# tusb8041_hub_test.net
KiCad netlist of a schematic drawn in EAGLE
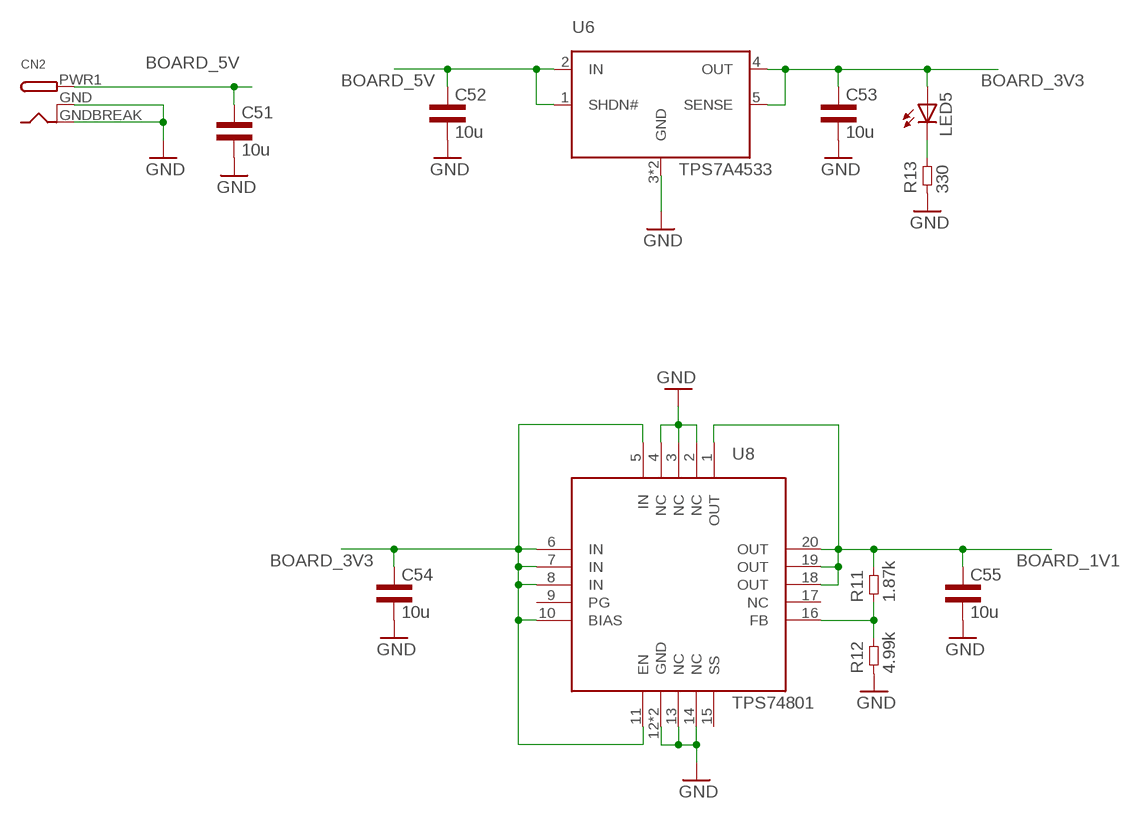
[diagram p0: schematic, sheet 1]
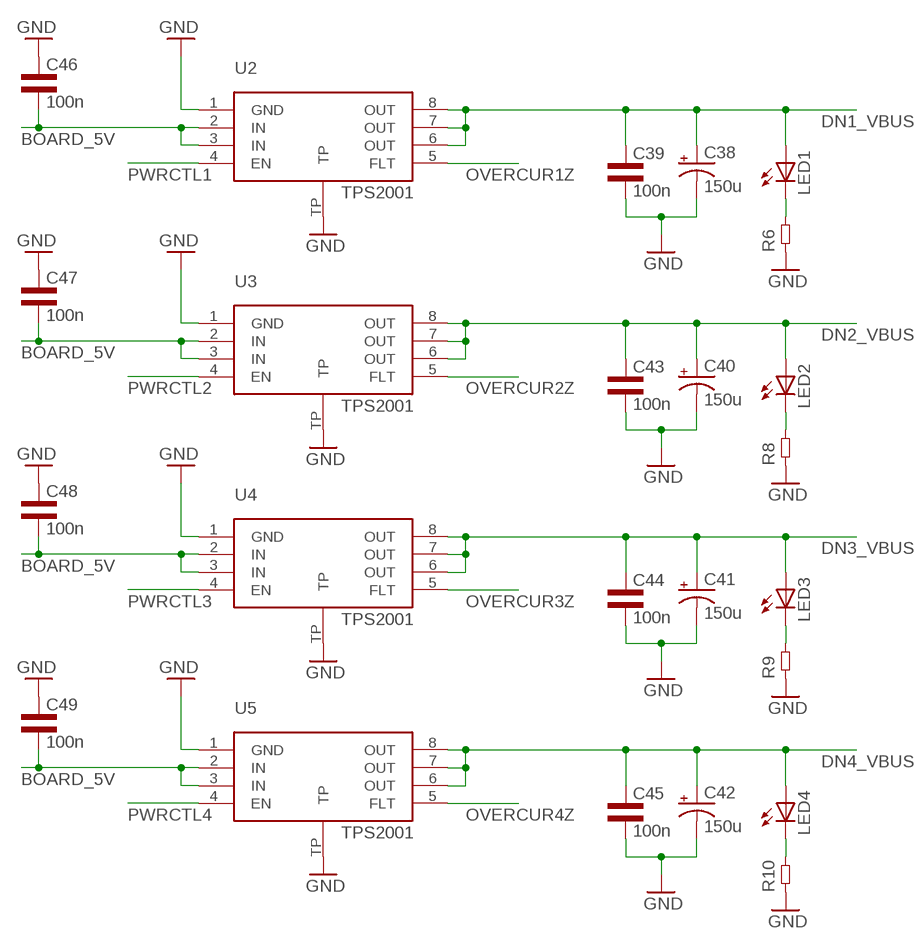
[diagram p1: schematic, sheet 2]
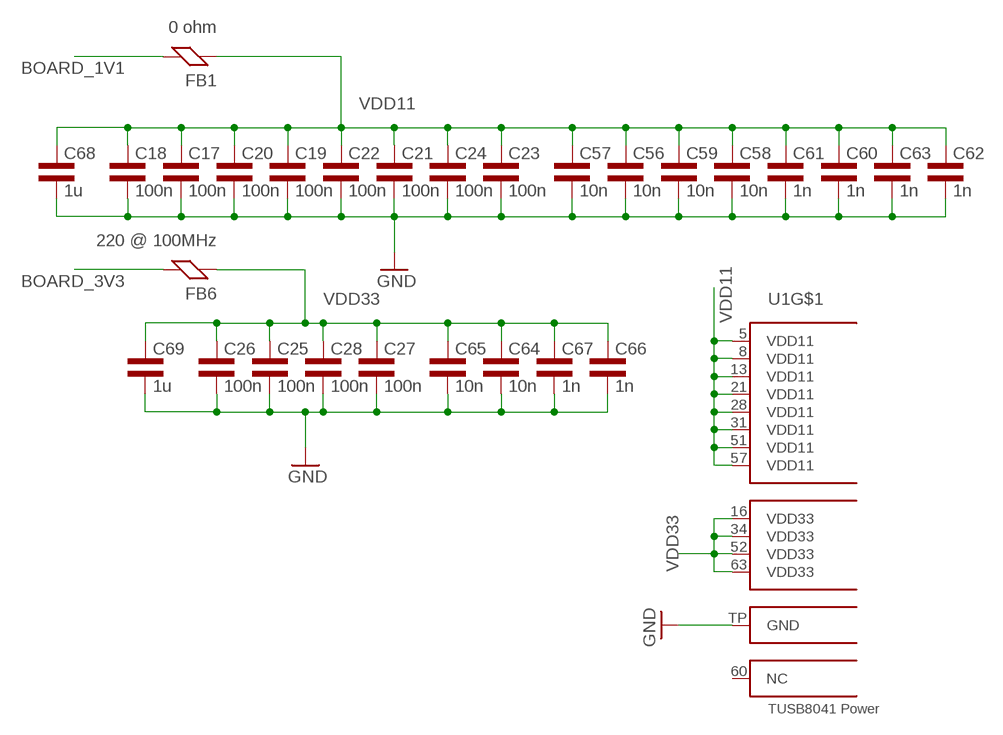
[diagram p2: schematic, sheet 3]
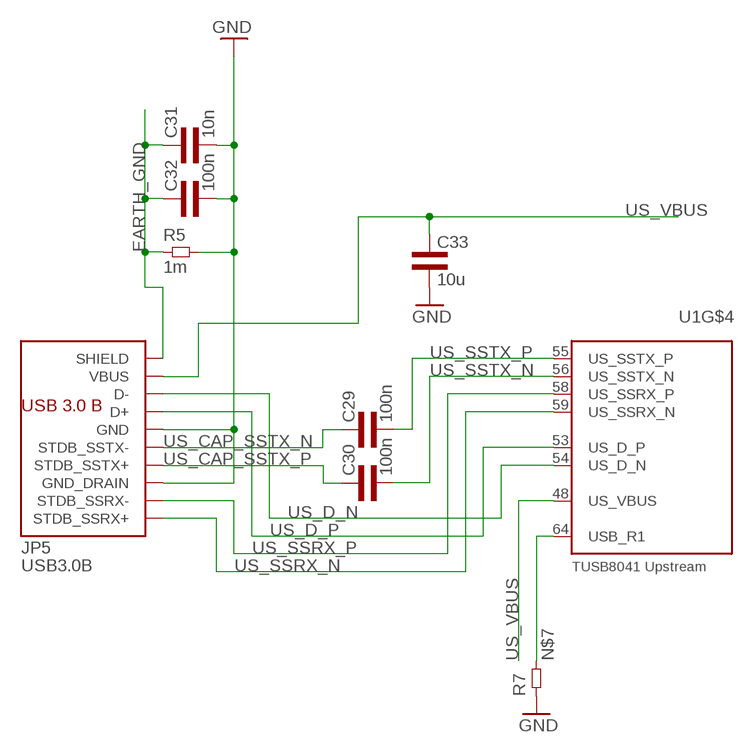
[diagram p3: schematic, sheet 4]
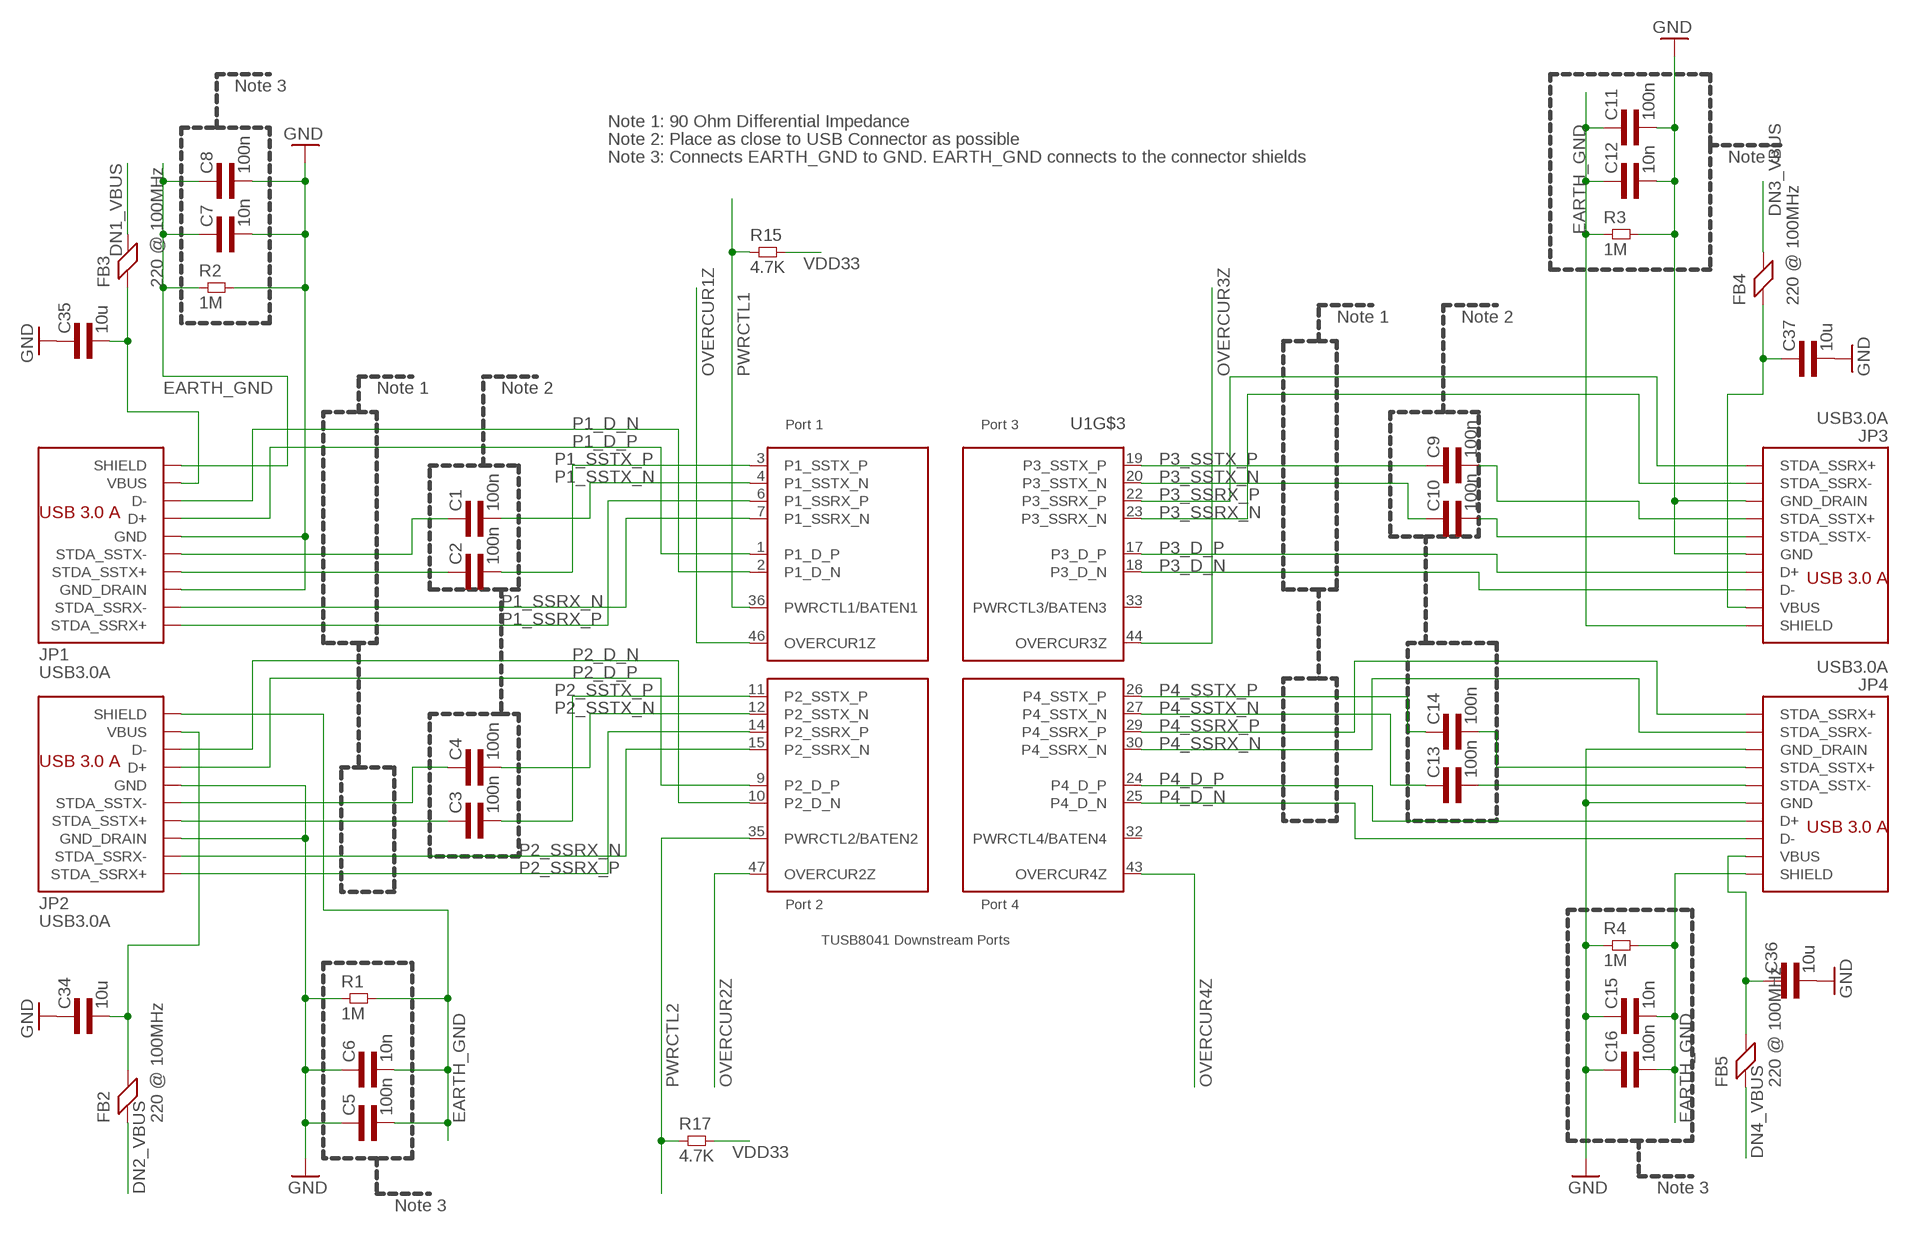
[diagram p4: schematic, sheet 5]
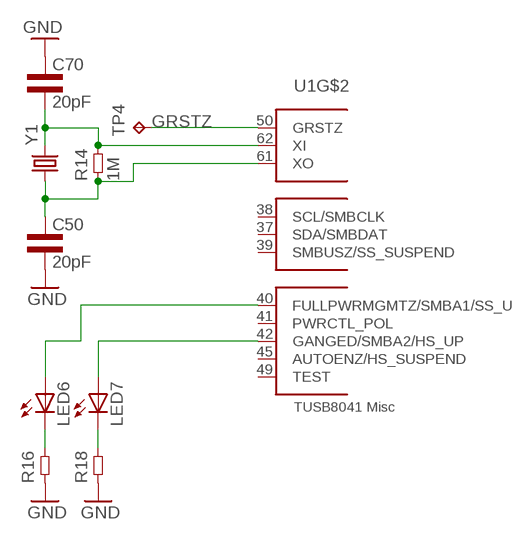
[diagram p5: schematic, sheet 6]

(export (version "E")
  (design (tool "Eeschema 10.0.6"))
  (components
    (comp (ref "C38")
      (value "150u")
      (footprint "eagle-import:CT7343")
      (libsource (lib "eagle-import") (part "CPOL-USCT7343"))
    )
    (comp (ref "C39")
      (value "100n")
      (footprint "eagle-import:0603L3")
      (libsource (lib "eagle-import") (part "CAP0603L3"))
    )
    (comp (ref "C40")
      (value "150u")
      (footprint "eagle-import:CT7343")
      (libsource (lib "eagle-import") (part "CPOL-USCT7343"))
    )
    (comp (ref "C41")
      (value "150u")
      (footprint "eagle-import:CT7343")
      (libsource (lib "eagle-import") (part "CPOL-USCT7343"))
    )
    (comp (ref "C42")
      (value "150u")
      (footprint "eagle-import:CT7343")
      (libsource (lib "eagle-import") (part "CPOL-USCT7343"))
    )
    (comp (ref "C43")
      (value "100n")
      (footprint "eagle-import:0603L3")
      (libsource (lib "eagle-import") (part "CAP0603L3"))
    )
    (comp (ref "C44")
      (value "100n")
      (footprint "eagle-import:0603L3")
      (libsource (lib "eagle-import") (part "CAP0603L3"))
    )
    (comp (ref "C45")
      (value "100n")
      (footprint "eagle-import:0603L3")
      (libsource (lib "eagle-import") (part "CAP0603L3"))
    )
    (comp (ref "C46")
      (value "100n")
      (footprint "eagle-import:0603L3")
      (libsource (lib "eagle-import") (part "CAP0603L3"))
    )
    (comp (ref "C47")
      (value "100n")
      (footprint "eagle-import:0603L3")
      (libsource (lib "eagle-import") (part "CAP0603L3"))
    )
    (comp (ref "C48")
      (value "100n")
      (footprint "eagle-import:0603L3")
      (libsource (lib "eagle-import") (part "CAP0603L3"))
    )
    (comp (ref "C49")
      (value "100n")
      (footprint "eagle-import:0603L3")
      (libsource (lib "eagle-import") (part "CAP0603L3"))
    )
    (comp (ref "LED1")
      (value "LEDCHIP-LED0603")
      (footprint "eagle-import:CHIP-LED0603")
      (libsource (lib "eagle-import") (part "LEDCHIP-LED0603"))
    )
    (comp (ref "LED2")
      (value "LEDCHIP-LED0603")
      (footprint "eagle-import:CHIP-LED0603")
      (libsource (lib "eagle-import") (part "LEDCHIP-LED0603"))
    )
    (comp (ref "LED3")
      (value "LEDCHIP-LED0603")
      (footprint "eagle-import:CHIP-LED0603")
      (libsource (lib "eagle-import") (part "LEDCHIP-LED0603"))
    )
    (comp (ref "LED4")
      (value "LEDCHIP-LED0603")
      (footprint "eagle-import:CHIP-LED0603")
      (libsource (lib "eagle-import") (part "LEDCHIP-LED0603"))
    )
    (comp (ref "R6")
      (value "RES0603L3")
      (footprint "eagle-import:0603L3")
      (libsource (lib "eagle-import") (part "RES0603L3"))
    )
    (comp (ref "R8")
      (value "RES0603L3")
      (footprint "eagle-import:0603L3")
      (libsource (lib "eagle-import") (part "RES0603L3"))
    )
    (comp (ref "R9")
      (value "RES0603L3")
      (footprint "eagle-import:0603L3")
      (libsource (lib "eagle-import") (part "RES0603L3"))
    )
    (comp (ref "R10")
      (value "RES0603L3")
      (footprint "eagle-import:0603L3")
      (libsource (lib "eagle-import") (part "RES0603L3"))
    )
    (comp (ref "U2")
      (value "TPS2001")
      (footprint "eagle-import:S-PDSO-G8")
      (libsource (lib "eagle-import") (part "TPS2001"))
    )
    (comp (ref "U3")
      (value "TPS2001")
      (footprint "eagle-import:S-PDSO-G8")
      (libsource (lib "eagle-import") (part "TPS2001"))
    )
    (comp (ref "U4")
      (value "TPS2001")
      (footprint "eagle-import:S-PDSO-G8")
      (libsource (lib "eagle-import") (part "TPS2001"))
    )
    (comp (ref "U5")
      (value "TPS2001")
      (footprint "eagle-import:S-PDSO-G8")
      (libsource (lib "eagle-import") (part "TPS2001"))
    )
    (comp (ref "C1")
      (value "100n")
      (footprint "eagle-import:0402L3")
      (libsource (lib "eagle-import") (part "CAP0402L3"))
    )
    (comp (ref "C2")
      (value "100n")
      (footprint "eagle-import:0402L3")
      (libsource (lib "eagle-import") (part "CAP0402L3"))
    )
    (comp (ref "C3")
      (value "100n")
      (footprint "eagle-import:0402L3")
      (libsource (lib "eagle-import") (part "CAP0402L3"))
    )
    (comp (ref "C4")
      (value "100n")
      (footprint "eagle-import:0402L3")
      (libsource (lib "eagle-import") (part "CAP0402L3"))
    )
    (comp (ref "C5")
      (value "100n")
      (footprint "eagle-import:0603L3")
      (libsource (lib "eagle-import") (part "CAP0603L3"))
    )
    (comp (ref "C6")
      (value "10n")
      (footprint "eagle-import:0603L3")
      (libsource (lib "eagle-import") (part "CAP0603L3"))
    )
    (comp (ref "C7")
      (value "10n")
      (footprint "eagle-import:0603L3")
      (libsource (lib "eagle-import") (part "CAP0603L3"))
    )
    (comp (ref "C8")
      (value "100n")
      (footprint "eagle-import:0603L3")
      (libsource (lib "eagle-import") (part "CAP0603L3"))
    )
    (comp (ref "C9")
      (value "100n")
      (footprint "eagle-import:0402L3")
      (libsource (lib "eagle-import") (part "CAP0402L3"))
    )
    (comp (ref "C10")
      (value "100n")
      (footprint "eagle-import:0402L3")
      (libsource (lib "eagle-import") (part "CAP0402L3"))
    )
    (comp (ref "C11")
      (value "100n")
      (footprint "eagle-import:0603L3")
      (libsource (lib "eagle-import") (part "CAP0603L3"))
    )
    (comp (ref "C12")
      (value "10n")
      (footprint "eagle-import:0603L3")
      (libsource (lib "eagle-import") (part "CAP0603L3"))
    )
    (comp (ref "C13")
      (value "100n")
      (footprint "eagle-import:0402L3")
      (libsource (lib "eagle-import") (part "CAP0402L3"))
    )
    (comp (ref "C14")
      (value "100n")
      (footprint "eagle-import:0402L3")
      (libsource (lib "eagle-import") (part "CAP0402L3"))
    )
    (comp (ref "C15")
      (value "10n")
      (footprint "eagle-import:0603L3")
      (libsource (lib "eagle-import") (part "CAP0603L3"))
    )
    (comp (ref "C16")
      (value "100n")
      (footprint "eagle-import:0603L3")
      (libsource (lib "eagle-import") (part "CAP0603L3"))
    )
    (comp (ref "C34")
      (value "10u")
      (footprint "eagle-import:1206L3")
      (libsource (lib "eagle-import") (part "CAP1206L3"))
    )
    (comp (ref "C35")
      (value "10u")
      (footprint "eagle-import:1206L3")
      (libsource (lib "eagle-import") (part "CAP1206L3"))
    )
    (comp (ref "C36")
      (value "10u")
      (footprint "eagle-import:1206L3")
      (libsource (lib "eagle-import") (part "CAP1206L3"))
    )
    (comp (ref "C37")
      (value "10u")
      (footprint "eagle-import:1206L3")
      (libsource (lib "eagle-import") (part "CAP1206L3"))
    )
    (comp (ref "FB2")
      (value "220 @ 100MHz")
      (footprint "eagle-import:0603L1")
      (libsource (lib "eagle-import") (part "FERRITE0603L1"))
    )
    (comp (ref "FB3")
      (value "220 @ 100MHz")
      (footprint "eagle-import:0603L1")
      (libsource (lib "eagle-import") (part "FERRITE0603L1"))
    )
    (comp (ref "FB4")
      (value "220 @ 100MHz")
      (footprint "eagle-import:0603L1")
      (libsource (lib "eagle-import") (part "FERRITE0603L1"))
    )
    (comp (ref "FB5")
      (value "220 @ 100MHz")
      (footprint "eagle-import:0603L1")
      (libsource (lib "eagle-import") (part "FERRITE0603L1"))
    )
    (comp (ref "JP1")
      (value "USB3.0A")
      (footprint "eagle-import:AMPHENOLUSB3.0A")
      (libsource (lib "eagle-import") (part "USB3.0A"))
    )
    (comp (ref "JP2")
      (value "USB3.0A")
      (footprint "eagle-import:AMPHENOLUSB3.0A")
      (libsource (lib "eagle-import") (part "USB3.0A"))
    )
    (comp (ref "JP3")
      (value "USB3.0A")
      (footprint "eagle-import:AMPHENOLUSB3.0A")
      (libsource (lib "eagle-import") (part "USB3.0A"))
    )
    (comp (ref "JP4")
      (value "USB3.0A")
      (footprint "eagle-import:AMPHENOLUSB3.0A")
      (libsource (lib "eagle-import") (part "USB3.0A"))
    )
    (comp (ref "R1")
      (value "1M")
      (footprint "eagle-import:0603L3")
      (libsource (lib "eagle-import") (part "RES0603L3"))
    )
    (comp (ref "R2")
      (value "1M")
      (footprint "eagle-import:0603L3")
      (libsource (lib "eagle-import") (part "RES0603L3"))
    )
    (comp (ref "R3")
      (value "1M")
      (footprint "eagle-import:0603L3")
      (libsource (lib "eagle-import") (part "RES0603L3"))
    )
    (comp (ref "R4")
      (value "1M")
      (footprint "eagle-import:0603L3")
      (libsource (lib "eagle-import") (part "RES0603L3"))
    )
    (comp (ref "R15")
      (value "4.7K")
      (footprint "eagle-import:0402L3")
      (libsource (lib "eagle-import") (part "RES0402L3"))
    )
    (comp (ref "R17")
      (value "4.7K")
      (footprint "eagle-import:0402L3")
      (libsource (lib "eagle-import") (part "RES0402L3"))
    )
    (comp (ref "U1")
      (value "TUSB8041")
      (footprint "eagle-import:VQFN64")
      (libsource (lib "eagle-import") (part "TUSB8041"))
    )
    (comp (ref "C50")
      (value "20pF")
      (footprint "eagle-import:0402L3")
      (libsource (lib "eagle-import") (part "CAP0402L3"))
    )
    (comp (ref "C70")
      (value "20pF")
      (footprint "eagle-import:0402L3")
      (libsource (lib "eagle-import") (part "CAP0402L3"))
    )
    (comp (ref "LED6")
      (value "LEDCHIPLED_0603")
      (footprint "eagle-import:CHIPLED_0603")
      (libsource (lib "eagle-import") (part "LEDCHIPLED_0603"))
    )
    (comp (ref "LED7")
      (value "LEDCHIPLED_0603")
      (footprint "eagle-import:CHIPLED_0603")
      (libsource (lib "eagle-import") (part "LEDCHIPLED_0603"))
    )
    (comp (ref "R14")
      (value "1M")
      (footprint "eagle-import:0402L3")
      (libsource (lib "eagle-import") (part "RES0402L3"))
    )
    (comp (ref "R16")
      (value "RES0402L3")
      (footprint "eagle-import:0402L3")
      (libsource (lib "eagle-import") (part "RES0402L3"))
    )
    (comp (ref "R18")
      (value "RES0402L3")
      (footprint "eagle-import:0402L3")
      (libsource (lib "eagle-import") (part "RES0402L3"))
    )
    (comp (ref "TP4")
      (value "TPTP10R")
      (footprint "eagle-import:TP10R")
      (libsource (lib "eagle-import") (part "TPTP10R"))
    )
    (comp (ref "Y1")
      (value "CRYSTALHC49US")
      (footprint "eagle-import:HC49US")
      (libsource (lib "eagle-import") (part "CRYSTALHC49US"))
    )
    (comp (ref "C29")
      (value "100n")
      (footprint "eagle-import:0402L3")
      (libsource (lib "eagle-import") (part "CAP0402L3"))
    )
    (comp (ref "C30")
      (value "100n")
      (footprint "eagle-import:0402L3")
      (libsource (lib "eagle-import") (part "CAP0402L3"))
    )
    (comp (ref "C31")
      (value "10n")
      (footprint "eagle-import:0603L3")
      (libsource (lib "eagle-import") (part "CAP0603L3"))
    )
    (comp (ref "C32")
      (value "100n")
      (footprint "eagle-import:0603L3")
      (libsource (lib "eagle-import") (part "CAP0603L3"))
    )
    (comp (ref "C33")
      (value "10u")
      (footprint "eagle-import:1206L3")
      (libsource (lib "eagle-import") (part "CAP1206L3"))
    )
    (comp (ref "JP5")
      (value "USB3.0B")
      (footprint "eagle-import:AMPHENOLUSB3.0B")
      (libsource (lib "eagle-import") (part "USB3.0B"))
    )
    (comp (ref "R5")
      (value "1m")
      (footprint "eagle-import:0603L3")
      (libsource (lib "eagle-import") (part "RES0603L3"))
    )
    (comp (ref "R7")
      (value "RES0402L3")
      (footprint "eagle-import:0402L3")
      (libsource (lib "eagle-import") (part "RES0402L3"))
    )
    (comp (ref "C51")
      (value "10u")
      (footprint "eagle-import:1206L3")
      (libsource (lib "eagle-import") (part "CAP1206L3"))
    )
    (comp (ref "C52")
      (value "10u")
      (footprint "eagle-import:1206L3")
      (libsource (lib "eagle-import") (part "CAP1206L3"))
    )
    (comp (ref "C53")
      (value "10u")
      (footprint "eagle-import:1206L3")
      (libsource (lib "eagle-import") (part "CAP1206L3"))
    )
    (comp (ref "C54")
      (value "10u")
      (footprint "eagle-import:1206L3")
      (libsource (lib "eagle-import") (part "CAP1206L3"))
    )
    (comp (ref "C55")
      (value "10u")
      (footprint "eagle-import:1206L3")
      (libsource (lib "eagle-import") (part "CAP1206L3"))
    )
    (comp (ref "CN2")
      (value "DCBARRELSMT")
      (footprint "eagle-import:DCJACK_2MM_SMT")
      (libsource (lib "eagle-import") (part "DCBARRELSMT"))
    )
    (comp (ref "LED5")
      (value "LEDCHIP-LED0603")
      (footprint "eagle-import:CHIP-LED0603")
      (libsource (lib "eagle-import") (part "LEDCHIP-LED0603"))
    )
    (comp (ref "R11")
      (value "1.87k")
      (footprint "eagle-import:0402L3")
      (libsource (lib "eagle-import") (part "RES0402L3"))
    )
    (comp (ref "R12")
      (value "4.99k")
      (footprint "eagle-import:0402L3")
      (libsource (lib "eagle-import") (part "RES0402L3"))
    )
    (comp (ref "R13")
      (value "330")
      (footprint "eagle-import:0603L3")
      (libsource (lib "eagle-import") (part "RES0603L3"))
    )
    (comp (ref "U6")
      (value "TPS7A4533")
      (footprint "eagle-import:R-PSFM-G5")
      (libsource (lib "eagle-import") (part "TPS7A4533"))
    )
    (comp (ref "U8")
      (value "TPS74801")
      (footprint "eagle-import:S-PVQFN-N20")
      (libsource (lib "eagle-import") (part "TPS74801"))
    )
    (comp (ref "C17")
      (value "100n")
      (footprint "eagle-import:0402L3")
      (libsource (lib "eagle-import") (part "CAP0402L3"))
    )
    (comp (ref "C18")
      (value "100n")
      (footprint "eagle-import:0402L3")
      (libsource (lib "eagle-import") (part "CAP0402L3"))
    )
    (comp (ref "C19")
      (value "100n")
      (footprint "eagle-import:0402L3")
      (libsource (lib "eagle-import") (part "CAP0402L3"))
    )
    (comp (ref "C20")
      (value "100n")
      (footprint "eagle-import:0402L3")
      (libsource (lib "eagle-import") (part "CAP0402L3"))
    )
    (comp (ref "C21")
      (value "100n")
      (footprint "eagle-import:0402L3")
      (libsource (lib "eagle-import") (part "CAP0402L3"))
    )
    (comp (ref "C22")
      (value "100n")
      (footprint "eagle-import:0402L3")
      (libsource (lib "eagle-import") (part "CAP0402L3"))
    )
    (comp (ref "C23")
      (value "100n")
      (footprint "eagle-import:0402L3")
      (libsource (lib "eagle-import") (part "CAP0402L3"))
    )
    (comp (ref "C24")
      (value "100n")
      (footprint "eagle-import:0402L3")
      (libsource (lib "eagle-import") (part "CAP0402L3"))
    )
    (comp (ref "C25")
      (value "100n")
      (footprint "eagle-import:0402L3")
      (libsource (lib "eagle-import") (part "CAP0402L3"))
    )
    (comp (ref "C26")
      (value "100n")
      (footprint "eagle-import:0402L3")
      (libsource (lib "eagle-import") (part "CAP0402L3"))
    )
    (comp (ref "C27")
      (value "100n")
      (footprint "eagle-import:0402L3")
      (libsource (lib "eagle-import") (part "CAP0402L3"))
    )
    (comp (ref "C28")
      (value "100n")
      (footprint "eagle-import:0402L3")
      (libsource (lib "eagle-import") (part "CAP0402L3"))
    )
    (comp (ref "C56")
      (value "10n")
      (footprint "eagle-import:0402L3")
      (libsource (lib "eagle-import") (part "CAP0402L3"))
    )
    (comp (ref "C57")
      (value "10n")
      (footprint "eagle-import:0402L3")
      (libsource (lib "eagle-import") (part "CAP0402L3"))
    )
    (comp (ref "C58")
      (value "10n")
      (footprint "eagle-import:0402L3")
      (libsource (lib "eagle-import") (part "CAP0402L3"))
    )
    (comp (ref "C59")
      (value "10n")
      (footprint "eagle-import:0402L3")
      (libsource (lib "eagle-import") (part "CAP0402L3"))
    )
    (comp (ref "C60")
      (value "1n")
      (footprint "eagle-import:0402L3")
      (libsource (lib "eagle-import") (part "CAP0402L3"))
    )
    (comp (ref "C61")
      (value "1n")
      (footprint "eagle-import:0402L3")
      (libsource (lib "eagle-import") (part "CAP0402L3"))
    )
    (comp (ref "C62")
      (value "1n")
      (footprint "eagle-import:0402L3")
      (libsource (lib "eagle-import") (part "CAP0402L3"))
    )
    (comp (ref "C63")
      (value "1n")
      (footprint "eagle-import:0402L3")
      (libsource (lib "eagle-import") (part "CAP0402L3"))
    )
    (comp (ref "C64")
      (value "10n")
      (footprint "eagle-import:0402L3")
      (libsource (lib "eagle-import") (part "CAP0402L3"))
    )
    (comp (ref "C65")
      (value "10n")
      (footprint "eagle-import:0402L3")
      (libsource (lib "eagle-import") (part "CAP0402L3"))
    )
    (comp (ref "C66")
      (value "1n")
      (footprint "eagle-import:0402L3")
      (libsource (lib "eagle-import") (part "CAP0402L3"))
    )
    (comp (ref "C67")
      (value "1n")
      (footprint "eagle-import:0402L3")
      (libsource (lib "eagle-import") (part "CAP0402L3"))
    )
    (comp (ref "C68")
      (value "1u")
      (footprint "eagle-import:0805L3")
      (libsource (lib "eagle-import") (part "CAP0805L3"))
    )
    (comp (ref "C69")
      (value "1u")
      (footprint "eagle-import:0805L3")
      (libsource (lib "eagle-import") (part "CAP0805L3"))
    )
    (comp (ref "FB1")
      (value "0 ohm")
      (footprint "eagle-import:0603L3")
      (libsource (lib "eagle-import") (part "FERRITE0603L3"))
    )
    (comp (ref "FB6")
      (value "220 @ 100MHz")
      (footprint "eagle-import:0603L3")
      (libsource (lib "eagle-import") (part "FERRITE0603L3"))
    )
  )
  (nets
    (net (code "1") (name "BOARD_1V1") (class "Default")
      (node (ref "C55") (pin "1") (pinfunction "1_1") (pintype "bidirectional"))
      (node (ref "FB1") (pin "P$2") (pinfunction "2_P$2") (pintype "bidirectional"))
      (node (ref "R11") (pin "P$2") (pinfunction "2_P$2") (pintype "bidirectional"))
      (node (ref "U8") (pin "1") (pinfunction "OUT_1") (pintype "bidirectional"))
      (node (ref "U8") (pin "18") (pinfunction "OUT_18") (pintype "bidirectional"))
      (node (ref "U8") (pin "19") (pinfunction "OUT_19") (pintype "bidirectional"))
      (node (ref "U8") (pin "20") (pinfunction "OUT_20") (pintype "bidirectional"))
    )
    (net (code "2") (name "BOARD_3V3") (class "Default")
      (node (ref "C53") (pin "1") (pinfunction "1_1") (pintype "bidirectional"))
      (node (ref "C54") (pin "1") (pinfunction "1_1") (pintype "bidirectional"))
      (node (ref "FB6") (pin "P$2") (pinfunction "2_P$2") (pintype "bidirectional"))
      (node (ref "LED5") (pin "A") (pinfunction "A_A") (pintype "passive"))
      (node (ref "U6") (pin "4") (pinfunction "OUT_4") (pintype "bidirectional"))
      (node (ref "U6") (pin "5") (pinfunction "SENSE_5") (pintype "bidirectional"))
      (node (ref "U8") (pin "10") (pinfunction "BIAS_10") (pintype "bidirectional"))
      (node (ref "U8") (pin "11") (pinfunction "EN_11") (pintype "bidirectional"))
      (node (ref "U8") (pin "5") (pinfunction "IN_5") (pintype "bidirectional"))
      (node (ref "U8") (pin "6") (pinfunction "IN_6") (pintype "bidirectional"))
      (node (ref "U8") (pin "7") (pinfunction "IN_7") (pintype "bidirectional"))
      (node (ref "U8") (pin "8") (pinfunction "IN_8") (pintype "bidirectional"))
    )
    (net (code "3") (name "BOARD_5V") (class "Default")
      (node (ref "C46") (pin "P$2") (pinfunction "2_P$2") (pintype "bidirectional"))
      (node (ref "C47") (pin "P$2") (pinfunction "2_P$2") (pintype "bidirectional"))
      (node (ref "C48") (pin "P$2") (pinfunction "2_P$2") (pintype "bidirectional"))
      (node (ref "C49") (pin "P$2") (pinfunction "2_P$2") (pintype "bidirectional"))
      (node (ref "C51") (pin "1") (pinfunction "1_1") (pintype "bidirectional"))
      (node (ref "C52") (pin "1") (pinfunction "1_1") (pintype "bidirectional"))
      (node (ref "CN2") (pin "PWR1") (pinfunction "PWR_PWR1") (pintype "power_in"))
      (node (ref "U2") (pin "2") (pinfunction "IN_2") (pintype "bidirectional"))
      (node (ref "U2") (pin "3") (pinfunction "IN_3") (pintype "bidirectional"))
      (node (ref "U3") (pin "2") (pinfunction "IN_2") (pintype "bidirectional"))
      (node (ref "U3") (pin "3") (pinfunction "IN_3") (pintype "bidirectional"))
      (node (ref "U4") (pin "2") (pinfunction "IN_2") (pintype "bidirectional"))
      (node (ref "U4") (pin "3") (pinfunction "IN_3") (pintype "bidirectional"))
      (node (ref "U5") (pin "2") (pinfunction "IN_2") (pintype "bidirectional"))
      (node (ref "U5") (pin "3") (pinfunction "IN_3") (pintype "bidirectional"))
      (node (ref "U6") (pin "1") (pinfunction "SHDN#_1") (pintype "bidirectional"))
      (node (ref "U6") (pin "2") (pinfunction "IN_2") (pintype "bidirectional"))
    )
    (net (code "4") (name "DN1_VBUS") (class "Default")
      (node (ref "C38") (pin "+") (pinfunction "+_+") (pintype "passive"))
      (node (ref "C39") (pin "P$1") (pinfunction "1_P$1") (pintype "bidirectional"))
      (node (ref "FB3") (pin "2") (pinfunction "2_2") (pintype "bidirectional"))
      (node (ref "LED1") (pin "A") (pinfunction "A_A") (pintype "passive"))
      (node (ref "U2") (pin "6") (pinfunction "OUT_6") (pintype "bidirectional"))
      (node (ref "U2") (pin "7") (pinfunction "OUT_7") (pintype "bidirectional"))
      (node (ref "U2") (pin "8") (pinfunction "OUT_8") (pintype "bidirectional"))
    )
    (net (code "5") (name "DN2_VBUS") (class "Default")
      (node (ref "C40") (pin "+") (pinfunction "+_+") (pintype "passive"))
      (node (ref "C43") (pin "P$1") (pinfunction "1_P$1") (pintype "bidirectional"))
      (node (ref "FB2") (pin "1") (pinfunction "1_1") (pintype "bidirectional"))
      (node (ref "LED2") (pin "A") (pinfunction "A_A") (pintype "passive"))
      (node (ref "U3") (pin "6") (pinfunction "OUT_6") (pintype "bidirectional"))
      (node (ref "U3") (pin "7") (pinfunction "OUT_7") (pintype "bidirectional"))
      (node (ref "U3") (pin "8") (pinfunction "OUT_8") (pintype "bidirectional"))
    )
    (net (code "6") (name "DN3_VBUS") (class "Default")
      (node (ref "C41") (pin "+") (pinfunction "+_+") (pintype "passive"))
      (node (ref "C44") (pin "P$1") (pinfunction "1_P$1") (pintype "bidirectional"))
      (node (ref "FB4") (pin "2") (pinfunction "2_2") (pintype "bidirectional"))
      (node (ref "LED3") (pin "A") (pinfunction "A_A") (pintype "passive"))
      (node (ref "U4") (pin "6") (pinfunction "OUT_6") (pintype "bidirectional"))
      (node (ref "U4") (pin "7") (pinfunction "OUT_7") (pintype "bidirectional"))
      (node (ref "U4") (pin "8") (pinfunction "OUT_8") (pintype "bidirectional"))
    )
    (net (code "7") (name "DN4_VBUS") (class "Default")
      (node (ref "C42") (pin "+") (pinfunction "+_+") (pintype "passive"))
      (node (ref "C45") (pin "P$1") (pinfunction "1_P$1") (pintype "bidirectional"))
      (node (ref "FB5") (pin "1") (pinfunction "1_1") (pintype "bidirectional"))
      (node (ref "LED4") (pin "A") (pinfunction "A_A") (pintype "passive"))
      (node (ref "U5") (pin "6") (pinfunction "OUT_6") (pintype "bidirectional"))
      (node (ref "U5") (pin "7") (pinfunction "OUT_7") (pintype "bidirectional"))
      (node (ref "U5") (pin "8") (pinfunction "OUT_8") (pintype "bidirectional"))
    )
    (net (code "8") (name "EARTH_GND") (class "Default")
      (node (ref "C11") (pin "P$1") (pinfunction "1_P$1") (pintype "bidirectional"))
      (node (ref "C12") (pin "P$1") (pinfunction "1_P$1") (pintype "bidirectional"))
      (node (ref "C15") (pin "P$2") (pinfunction "2_P$2") (pintype "bidirectional"))
      (node (ref "C16") (pin "P$2") (pinfunction "2_P$2") (pintype "bidirectional"))
      (node (ref "C31") (pin "P$1") (pinfunction "1_P$1") (pintype "bidirectional"))
      (node (ref "C32") (pin "P$1") (pinfunction "1_P$1") (pintype "bidirectional"))
      (node (ref "C5") (pin "P$2") (pinfunction "2_P$2") (pintype "bidirectional"))
      (node (ref "C6") (pin "P$2") (pinfunction "2_P$2") (pintype "bidirectional"))
      (node (ref "C7") (pin "P$1") (pinfunction "1_P$1") (pintype "bidirectional"))
      (node (ref "C8") (pin "P$1") (pinfunction "1_P$1") (pintype "bidirectional"))
      (node (ref "JP1") (pin "10@1") (pinfunction "SHIELD_10@1") (pintype "bidirectional"))
      (node (ref "JP1") (pin "10@2") (pinfunction "SHIELD_10@2") (pintype "bidirectional"))
      (node (ref "JP2") (pin "10@1") (pinfunction "SHIELD_10@1") (pintype "bidirectional"))
      (node (ref "JP2") (pin "10@2") (pinfunction "SHIELD_10@2") (pintype "bidirectional"))
      (node (ref "JP3") (pin "10@1") (pinfunction "SHIELD_10@1") (pintype "bidirectional"))
      (node (ref "JP3") (pin "10@2") (pinfunction "SHIELD_10@2") (pintype "bidirectional"))
      (node (ref "JP4") (pin "10@1") (pinfunction "SHIELD_10@1") (pintype "bidirectional"))
      (node (ref "JP4") (pin "10@2") (pinfunction "SHIELD_10@2") (pintype "bidirectional"))
      (node (ref "JP5") (pin "10@1") (pinfunction "SHIELD_10@1") (pintype "bidirectional"))
      (node (ref "JP5") (pin "10@2") (pinfunction "SHIELD_10@2") (pintype "bidirectional"))
      (node (ref "R1") (pin "P$2") (pinfunction "2_P$2") (pintype "bidirectional"))
      (node (ref "R2") (pin "P$1") (pinfunction "1_P$1") (pintype "bidirectional"))
      (node (ref "R3") (pin "P$1") (pinfunction "1_P$1") (pintype "bidirectional"))
      (node (ref "R4") (pin "P$2") (pinfunction "2_P$2") (pintype "bidirectional"))
      (node (ref "R5") (pin "P$1") (pinfunction "1_P$1") (pintype "bidirectional"))
    )
    (net (code "9") (name "GND") (class "Default")
      (node (ref "C11") (pin "P$2") (pinfunction "2_P$2") (pintype "bidirectional"))
      (node (ref "C12") (pin "P$2") (pinfunction "2_P$2") (pintype "bidirectional"))
      (node (ref "C15") (pin "P$1") (pinfunction "1_P$1") (pintype "bidirectional"))
      (node (ref "C16") (pin "P$1") (pinfunction "1_P$1") (pintype "bidirectional"))
      (node (ref "C17") (pin "P$2") (pinfunction "2_P$2") (pintype "bidirectional"))
      (node (ref "C18") (pin "P$2") (pinfunction "2_P$2") (pintype "bidirectional"))
      (node (ref "C19") (pin "P$2") (pinfunction "2_P$2") (pintype "bidirectional"))
      (node (ref "C20") (pin "P$2") (pinfunction "2_P$2") (pintype "bidirectional"))
      (node (ref "C21") (pin "P$2") (pinfunction "2_P$2") (pintype "bidirectional"))
      (node (ref "C22") (pin "P$2") (pinfunction "2_P$2") (pintype "bidirectional"))
      (node (ref "C23") (pin "P$2") (pinfunction "2_P$2") (pintype "bidirectional"))
      (node (ref "C24") (pin "P$2") (pinfunction "2_P$2") (pintype "bidirectional"))
      (node (ref "C25") (pin "P$2") (pinfunction "2_P$2") (pintype "bidirectional"))
      (node (ref "C26") (pin "P$2") (pinfunction "2_P$2") (pintype "bidirectional"))
      (node (ref "C27") (pin "P$2") (pinfunction "2_P$2") (pintype "bidirectional"))
      (node (ref "C28") (pin "P$2") (pinfunction "2_P$2") (pintype "bidirectional"))
      (node (ref "C31") (pin "P$2") (pinfunction "2_P$2") (pintype "bidirectional"))
      (node (ref "C32") (pin "P$2") (pinfunction "2_P$2") (pintype "bidirectional"))
      (node (ref "C33") (pin "2") (pinfunction "2_2") (pintype "bidirectional"))
      (node (ref "C34") (pin "1") (pinfunction "1_1") (pintype "bidirectional"))
      (node (ref "C35") (pin "1") (pinfunction "1_1") (pintype "bidirectional"))
      (node (ref "C36") (pin "2") (pinfunction "2_2") (pintype "bidirectional"))
      (node (ref "C37") (pin "2") (pinfunction "2_2") (pintype "bidirectional"))
      (node (ref "C38") (pin "-") (pinfunction "-_-") (pintype "passive"))
      (node (ref "C39") (pin "P$2") (pinfunction "2_P$2") (pintype "bidirectional"))
      (node (ref "C40") (pin "-") (pinfunction "-_-") (pintype "passive"))
      (node (ref "C41") (pin "-") (pinfunction "-_-") (pintype "passive"))
      (node (ref "C42") (pin "-") (pinfunction "-_-") (pintype "passive"))
      (node (ref "C43") (pin "P$2") (pinfunction "2_P$2") (pintype "bidirectional"))
      (node (ref "C44") (pin "P$2") (pinfunction "2_P$2") (pintype "bidirectional"))
      (node (ref "C45") (pin "P$2") (pinfunction "2_P$2") (pintype "bidirectional"))
      (node (ref "C46") (pin "P$1") (pinfunction "1_P$1") (pintype "bidirectional"))
      (node (ref "C47") (pin "P$1") (pinfunction "1_P$1") (pintype "bidirectional"))
      (node (ref "C48") (pin "P$1") (pinfunction "1_P$1") (pintype "bidirectional"))
      (node (ref "C49") (pin "P$1") (pinfunction "1_P$1") (pintype "bidirectional"))
      (node (ref "C5") (pin "P$1") (pinfunction "1_P$1") (pintype "bidirectional"))
      (node (ref "C50") (pin "P$2") (pinfunction "2_P$2") (pintype "bidirectional"))
      (node (ref "C51") (pin "2") (pinfunction "2_2") (pintype "bidirectional"))
      (node (ref "C52") (pin "2") (pinfunction "2_2") (pintype "bidirectional"))
      (node (ref "C53") (pin "2") (pinfunction "2_2") (pintype "bidirectional"))
      (node (ref "C54") (pin "2") (pinfunction "2_2") (pintype "bidirectional"))
      (node (ref "C55") (pin "2") (pinfunction "2_2") (pintype "bidirectional"))
      (node (ref "C56") (pin "P$2") (pinfunction "2_P$2") (pintype "bidirectional"))
      (node (ref "C57") (pin "P$2") (pinfunction "2_P$2") (pintype "bidirectional"))
      (node (ref "C58") (pin "P$2") (pinfunction "2_P$2") (pintype "bidirectional"))
      (node (ref "C59") (pin "P$2") (pinfunction "2_P$2") (pintype "bidirectional"))
      (node (ref "C6") (pin "P$1") (pinfunction "1_P$1") (pintype "bidirectional"))
      (node (ref "C60") (pin "P$2") (pinfunction "2_P$2") (pintype "bidirectional"))
      (node (ref "C61") (pin "P$2") (pinfunction "2_P$2") (pintype "bidirectional"))
      (node (ref "C62") (pin "P$2") (pinfunction "2_P$2") (pintype "bidirectional"))
      (node (ref "C63") (pin "P$2") (pinfunction "2_P$2") (pintype "bidirectional"))
      (node (ref "C64") (pin "P$2") (pinfunction "2_P$2") (pintype "bidirectional"))
      (node (ref "C65") (pin "P$2") (pinfunction "2_P$2") (pintype "bidirectional"))
      (node (ref "C66") (pin "P$2") (pinfunction "2_P$2") (pintype "bidirectional"))
      (node (ref "C67") (pin "P$2") (pinfunction "2_P$2") (pintype "bidirectional"))
      (node (ref "C68") (pin "2") (pinfunction "2_2") (pintype "bidirectional"))
      (node (ref "C69") (pin "2") (pinfunction "2_2") (pintype "bidirectional"))
      (node (ref "C7") (pin "P$2") (pinfunction "2_P$2") (pintype "bidirectional"))
      (node (ref "C70") (pin "P$1") (pinfunction "1_P$1") (pintype "bidirectional"))
      (node (ref "C8") (pin "P$2") (pinfunction "2_P$2") (pintype "bidirectional"))
      (node (ref "CN2") (pin "GND") (pinfunction "GNDBREAK_GND") (pintype "power_in"))
      (node (ref "CN2") (pin "GNDBREAK") (pinfunction "GND_GNDBREAK") (pintype "power_in"))
      (node (ref "JP1") (pin "4") (pinfunction "GND_4") (pintype "bidirectional"))
      (node (ref "JP1") (pin "7") (pinfunction "GND_DRAIN_7") (pintype "bidirectional"))
      (node (ref "JP2") (pin "4") (pinfunction "GND_4") (pintype "bidirectional"))
      (node (ref "JP2") (pin "7") (pinfunction "GND_DRAIN_7") (pintype "bidirectional"))
      (node (ref "JP3") (pin "4") (pinfunction "GND_4") (pintype "bidirectional"))
      (node (ref "JP3") (pin "7") (pinfunction "GND_DRAIN_7") (pintype "bidirectional"))
      (node (ref "JP4") (pin "4") (pinfunction "GND_4") (pintype "bidirectional"))
      (node (ref "JP4") (pin "7") (pinfunction "GND_DRAIN_7") (pintype "bidirectional"))
      (node (ref "JP5") (pin "4") (pinfunction "GND_4") (pintype "bidirectional"))
      (node (ref "JP5") (pin "7") (pinfunction "GND_DRAIN_7") (pintype "bidirectional"))
      (node (ref "R1") (pin "P$1") (pinfunction "1_P$1") (pintype "bidirectional"))
      (node (ref "R10") (pin "P$1") (pinfunction "1_P$1") (pintype "bidirectional"))
      (node (ref "R12") (pin "P$1") (pinfunction "1_P$1") (pintype "bidirectional"))
      (node (ref "R13") (pin "P$1") (pinfunction "1_P$1") (pintype "bidirectional"))
      (node (ref "R16") (pin "P$1") (pinfunction "1_P$1") (pintype "bidirectional"))
      (node (ref "R18") (pin "P$1") (pinfunction "1_P$1") (pintype "bidirectional"))
      (node (ref "R2") (pin "P$2") (pinfunction "2_P$2") (pintype "bidirectional"))
      (node (ref "R3") (pin "P$2") (pinfunction "2_P$2") (pintype "bidirectional"))
      (node (ref "R4") (pin "P$1") (pinfunction "1_P$1") (pintype "bidirectional"))
      (node (ref "R5") (pin "P$2") (pinfunction "2_P$2") (pintype "bidirectional"))
      (node (ref "R6") (pin "P$1") (pinfunction "1_P$1") (pintype "bidirectional"))
      (node (ref "R7") (pin "P$1") (pinfunction "1_P$1") (pintype "bidirectional"))
      (node (ref "R8") (pin "P$1") (pinfunction "1_P$1") (pintype "bidirectional"))
      (node (ref "R9") (pin "P$1") (pinfunction "1_P$1") (pintype "bidirectional"))
      (node (ref "U1") (pin "TP") (pinfunction "GND_TP") (pintype "bidirectional"))
      (node (ref "U2") (pin "1") (pinfunction "GND_1") (pintype "bidirectional"))
      (node (ref "U2") (pin "TP") (pinfunction "TP_TP") (pintype "bidirectional"))
      (node (ref "U3") (pin "1") (pinfunction "GND_1") (pintype "bidirectional"))
      (node (ref "U3") (pin "TP") (pinfunction "TP_TP") (pintype "bidirectional"))
      (node (ref "U4") (pin "1") (pinfunction "GND_1") (pintype "bidirectional"))
      (node (ref "U4") (pin "TP") (pinfunction "TP_TP") (pintype "bidirectional"))
      (node (ref "U5") (pin "1") (pinfunction "GND_1") (pintype "bidirectional"))
      (node (ref "U5") (pin "TP") (pinfunction "TP_TP") (pintype "bidirectional"))
      (node (ref "U6") (pin "3") (pinfunction "GND_3") (pintype "bidirectional"))
      (node (ref "U6") (pin "TP") (pinfunction "GND_TP") (pintype "bidirectional"))
      (node (ref "U8") (pin "12") (pinfunction "GND_12") (pintype "bidirectional"))
      (node (ref "U8") (pin "13") (pinfunction "NC_13") (pintype "bidirectional"))
      (node (ref "U8") (pin "14") (pinfunction "NC_14") (pintype "bidirectional"))
      (node (ref "U8") (pin "2") (pinfunction "NC_2") (pintype "bidirectional"))
      (node (ref "U8") (pin "3") (pinfunction "NC_3") (pintype "bidirectional"))
      (node (ref "U8") (pin "4") (pinfunction "NC_4") (pintype "bidirectional"))
      (node (ref "U8") (pin "TP") (pinfunction "GND_TP") (pintype "bidirectional"))
    )
    (net (code "10") (name "GRSTZ") (class "Default")
      (node (ref "TP4") (pin "TP") (pinfunction "TP_TP") (pintype "input"))
      (node (ref "U1") (pin "50") (pinfunction "GRSTZ_50") (pintype "bidirectional"))
    )
    (net (code "11") (name "N$7") (class "Default")
      (node (ref "R7") (pin "P$2") (pinfunction "2_P$2") (pintype "bidirectional"))
      (node (ref "U1") (pin "64") (pinfunction "USB_R1_64") (pintype "bidirectional"))
    )
    (net (code "12") (name "Net-(C1-1)") (class "Default")
      (node (ref "C1") (pin "P$1") (pinfunction "1_P$1") (pintype "bidirectional"))
      (node (ref "JP1") (pin "8") (pinfunction "STDA_SSTX-_8") (pintype "bidirectional"))
    )
    (net (code "13") (name "Net-(C2-1)") (class "Default")
      (node (ref "C2") (pin "P$1") (pinfunction "1_P$1") (pintype "bidirectional"))
      (node (ref "JP1") (pin "9") (pinfunction "STDA_SSTX+_9") (pintype "bidirectional"))
    )
    (net (code "14") (name "Net-(C3-1)") (class "Default")
      (node (ref "C3") (pin "P$1") (pinfunction "1_P$1") (pintype "bidirectional"))
      (node (ref "JP2") (pin "9") (pinfunction "STDA_SSTX+_9") (pintype "bidirectional"))
    )
    (net (code "15") (name "Net-(C4-1)") (class "Default")
      (node (ref "C4") (pin "P$1") (pinfunction "1_P$1") (pintype "bidirectional"))
      (node (ref "JP2") (pin "8") (pinfunction "STDA_SSTX-_8") (pintype "bidirectional"))
    )
    (net (code "16") (name "Net-(C9-2)") (class "Default")
      (node (ref "C9") (pin "P$2") (pinfunction "2_P$2") (pintype "bidirectional"))
      (node (ref "JP3") (pin "9") (pinfunction "STDA_SSTX+_9") (pintype "bidirectional"))
    )
    (net (code "17") (name "Net-(C10-2)") (class "Default")
      (node (ref "C10") (pin "P$2") (pinfunction "2_P$2") (pintype "bidirectional"))
      (node (ref "JP3") (pin "8") (pinfunction "STDA_SSTX-_8") (pintype "bidirectional"))
    )
    (net (code "18") (name "Net-(C13-2)") (class "Default")
      (node (ref "C13") (pin "P$2") (pinfunction "2_P$2") (pintype "bidirectional"))
      (node (ref "JP4") (pin "8") (pinfunction "STDA_SSTX-_8") (pintype "bidirectional"))
    )
    (net (code "19") (name "Net-(C14-2)") (class "Default")
      (node (ref "C14") (pin "P$2") (pinfunction "2_P$2") (pintype "bidirectional"))
      (node (ref "JP4") (pin "9") (pinfunction "STDA_SSTX+_9") (pintype "bidirectional"))
    )
    (net (code "20") (name "Net-(C50-1)") (class "Default")
      (node (ref "C50") (pin "P$1") (pinfunction "1_P$1") (pintype "bidirectional"))
      (node (ref "R14") (pin "P$1") (pinfunction "1_P$1") (pintype "bidirectional"))
      (node (ref "U1") (pin "61") (pinfunction "XO_61") (pintype "bidirectional"))
      (node (ref "Y1") (pin "1") (pinfunction "1_1") (pintype "passive"))
    )
    (net (code "21") (name "Net-(C70-2)") (class "Default")
      (node (ref "C70") (pin "P$2") (pinfunction "2_P$2") (pintype "bidirectional"))
      (node (ref "R14") (pin "P$2") (pinfunction "2_P$2") (pintype "bidirectional"))
      (node (ref "U1") (pin "62") (pinfunction "XI_62") (pintype "bidirectional"))
      (node (ref "Y1") (pin "2") (pinfunction "2_2") (pintype "passive"))
    )
    (net (code "22") (name "Net-(JP1-VBUS)") (class "Default")
      (node (ref "C35") (pin "2") (pinfunction "2_2") (pintype "bidirectional"))
      (node (ref "FB3") (pin "1") (pinfunction "1_1") (pintype "bidirectional"))
      (node (ref "JP1") (pin "1") (pinfunction "VBUS_1") (pintype "bidirectional"))
    )
    (net (code "23") (name "Net-(JP2-VBUS)") (class "Default")
      (node (ref "C34") (pin "2") (pinfunction "2_2") (pintype "bidirectional"))
      (node (ref "FB2") (pin "2") (pinfunction "2_2") (pintype "bidirectional"))
      (node (ref "JP2") (pin "1") (pinfunction "VBUS_1") (pintype "bidirectional"))
    )
    (net (code "24") (name "Net-(JP3-VBUS)") (class "Default")
      (node (ref "C37") (pin "1") (pinfunction "1_1") (pintype "bidirectional"))
      (node (ref "FB4") (pin "1") (pinfunction "1_1") (pintype "bidirectional"))
      (node (ref "JP3") (pin "1") (pinfunction "VBUS_1") (pintype "bidirectional"))
    )
    (net (code "25") (name "Net-(JP4-VBUS)") (class "Default")
      (node (ref "C36") (pin "1") (pinfunction "1_1") (pintype "bidirectional"))
      (node (ref "FB5") (pin "2") (pinfunction "2_2") (pintype "bidirectional"))
      (node (ref "JP4") (pin "1") (pinfunction "VBUS_1") (pintype "bidirectional"))
    )
    (net (code "26") (name "Net-(R6-2)") (class "Default")
      (node (ref "LED1") (pin "C") (pinfunction "C_C") (pintype "passive"))
      (node (ref "R6") (pin "P$2") (pinfunction "2_P$2") (pintype "bidirectional"))
    )
    (net (code "27") (name "Net-(R8-2)") (class "Default")
      (node (ref "LED2") (pin "C") (pinfunction "C_C") (pintype "passive"))
      (node (ref "R8") (pin "P$2") (pinfunction "2_P$2") (pintype "bidirectional"))
    )
    (net (code "28") (name "Net-(R9-2)") (class "Default")
      (node (ref "LED3") (pin "C") (pinfunction "C_C") (pintype "passive"))
      (node (ref "R9") (pin "P$2") (pinfunction "2_P$2") (pintype "bidirectional"))
    )
    (net (code "29") (name "Net-(R10-2)") (class "Default")
      (node (ref "LED4") (pin "C") (pinfunction "C_C") (pintype "passive"))
      (node (ref "R10") (pin "P$2") (pinfunction "2_P$2") (pintype "bidirectional"))
    )
    (net (code "30") (name "Net-(R11-1)") (class "Default")
      (node (ref "R11") (pin "P$1") (pinfunction "1_P$1") (pintype "bidirectional"))
      (node (ref "R12") (pin "P$2") (pinfunction "2_P$2") (pintype "bidirectional"))
      (node (ref "U8") (pin "16") (pinfunction "FB_16") (pintype "bidirectional"))
    )
    (net (code "31") (name "Net-(R13-2)") (class "Default")
      (node (ref "LED5") (pin "C") (pinfunction "C_C") (pintype "passive"))
      (node (ref "R13") (pin "P$2") (pinfunction "2_P$2") (pintype "bidirectional"))
    )
    (net (code "32") (name "Net-(R16-2)") (class "Default")
      (node (ref "LED6") (pin "C") (pinfunction "C_C") (pintype "passive"))
      (node (ref "R16") (pin "P$2") (pinfunction "2_P$2") (pintype "bidirectional"))
    )
    (net (code "33") (name "Net-(R18-2)") (class "Default")
      (node (ref "LED7") (pin "C") (pinfunction "C_C") (pintype "passive"))
      (node (ref "R18") (pin "P$2") (pinfunction "2_P$2") (pintype "bidirectional"))
    )
    (net (code "34") (name "Net-(U1B-FULLPWRMGMTZ{slash}SMBA1{slash}SS_UP)") (class "Default")
      (node (ref "LED6") (pin "A") (pinfunction "A_A") (pintype "passive"))
      (node (ref "U1") (pin "40") (pinfunction "FULLPWRMGMTZ/SMBA1/SS_UP_40") (pintype "bidirectional"))
    )
    (net (code "35") (name "Net-(U1B-GANGED{slash}SMBA2{slash}HS_UP)") (class "Default")
      (node (ref "LED7") (pin "A") (pinfunction "A_A") (pintype "passive"))
      (node (ref "U1") (pin "42") (pinfunction "GANGED/SMBA2/HS_UP_42") (pintype "bidirectional"))
    )
    (net (code "36") (name "OVERCUR1Z") (class "Default")
      (node (ref "U1") (pin "46") (pinfunction "OVERCUR1Z_46") (pintype "bidirectional"))
      (node (ref "U2") (pin "5") (pinfunction "FLT_5") (pintype "bidirectional"))
    )
    (net (code "37") (name "OVERCUR2Z") (class "Default")
      (node (ref "U1") (pin "47") (pinfunction "OVERCUR2Z_47") (pintype "bidirectional"))
      (node (ref "U3") (pin "5") (pinfunction "FLT_5") (pintype "bidirectional"))
    )
    (net (code "38") (name "OVERCUR3Z") (class "Default")
      (node (ref "U1") (pin "44") (pinfunction "OVERCUR3Z_44") (pintype "bidirectional"))
      (node (ref "U4") (pin "5") (pinfunction "FLT_5") (pintype "bidirectional"))
    )
    (net (code "39") (name "OVERCUR4Z") (class "Default")
      (node (ref "U1") (pin "43") (pinfunction "OVERCUR4Z_43") (pintype "bidirectional"))
      (node (ref "U5") (pin "5") (pinfunction "FLT_5") (pintype "bidirectional"))
    )
    (net (code "40") (name "P1_D_N") (class "Default")
      (node (ref "JP1") (pin "2") (pinfunction "D-_2") (pintype "bidirectional"))
      (node (ref "U1") (pin "2") (pinfunction "P1_D_N_2") (pintype "bidirectional"))
    )
    (net (code "41") (name "P1_D_P") (class "Default")
      (node (ref "JP1") (pin "3") (pinfunction "D+_3") (pintype "bidirectional"))
      (node (ref "U1") (pin "1") (pinfunction "P1_D_P_1") (pintype "bidirectional"))
    )
    (net (code "42") (name "P1_SSRX_N") (class "Default")
      (node (ref "JP1") (pin "5") (pinfunction "STDA_SSRX-_5") (pintype "bidirectional"))
      (node (ref "U1") (pin "7") (pinfunction "P1_SSRX_N_7") (pintype "bidirectional"))
    )
    (net (code "43") (name "P1_SSRX_P") (class "Default")
      (node (ref "JP1") (pin "6") (pinfunction "STDA_SSRX+_6") (pintype "bidirectional"))
      (node (ref "U1") (pin "6") (pinfunction "P1_SSRX_P_6") (pintype "bidirectional"))
    )
    (net (code "44") (name "P1_SSTX_N") (class "Default")
      (node (ref "C1") (pin "P$2") (pinfunction "2_P$2") (pintype "bidirectional"))
      (node (ref "U1") (pin "4") (pinfunction "P1_SSTX_N_4") (pintype "bidirectional"))
    )
    (net (code "45") (name "P1_SSTX_P") (class "Default")
      (node (ref "C2") (pin "P$2") (pinfunction "2_P$2") (pintype "bidirectional"))
      (node (ref "U1") (pin "3") (pinfunction "P1_SSTX_P_3") (pintype "bidirectional"))
    )
    (net (code "46") (name "P2_D_N") (class "Default")
      (node (ref "JP2") (pin "2") (pinfunction "D-_2") (pintype "bidirectional"))
      (node (ref "U1") (pin "10") (pinfunction "P2_D_N_10") (pintype "bidirectional"))
    )
    (net (code "47") (name "P2_D_P") (class "Default")
      (node (ref "JP2") (pin "3") (pinfunction "D+_3") (pintype "bidirectional"))
      (node (ref "U1") (pin "9") (pinfunction "P2_D_P_9") (pintype "bidirectional"))
    )
    (net (code "48") (name "P2_SSRX_N") (class "Default")
      (node (ref "JP2") (pin "5") (pinfunction "STDA_SSRX-_5") (pintype "bidirectional"))
      (node (ref "U1") (pin "15") (pinfunction "P2_SSRX_N_15") (pintype "bidirectional"))
    )
    (net (code "49") (name "P2_SSRX_P") (class "Default")
      (node (ref "JP2") (pin "6") (pinfunction "STDA_SSRX+_6") (pintype "bidirectional"))
      (node (ref "U1") (pin "14") (pinfunction "P2_SSRX_P_14") (pintype "bidirectional"))
    )
    (net (code "50") (name "P2_SSTX_N") (class "Default")
      (node (ref "C4") (pin "P$2") (pinfunction "2_P$2") (pintype "bidirectional"))
      (node (ref "U1") (pin "12") (pinfunction "P2_SSTX_N_12") (pintype "bidirectional"))
    )
    (net (code "51") (name "P2_SSTX_P") (class "Default")
      (node (ref "C3") (pin "P$2") (pinfunction "2_P$2") (pintype "bidirectional"))
      (node (ref "U1") (pin "11") (pinfunction "P2_SSTX_P_11") (pintype "bidirectional"))
    )
    (net (code "52") (name "P3_D_N") (class "Default")
      (node (ref "JP3") (pin "2") (pinfunction "D-_2") (pintype "bidirectional"))
      (node (ref "U1") (pin "18") (pinfunction "P3_D_N_18") (pintype "bidirectional"))
    )
    (net (code "53") (name "P3_D_P") (class "Default")
      (node (ref "JP3") (pin "3") (pinfunction "D+_3") (pintype "bidirectional"))
      (node (ref "U1") (pin "17") (pinfunction "P3_D_P_17") (pintype "bidirectional"))
    )
    (net (code "54") (name "P3_SSRX_N") (class "Default")
      (node (ref "JP3") (pin "5") (pinfunction "STDA_SSRX-_5") (pintype "bidirectional"))
      (node (ref "U1") (pin "23") (pinfunction "P3_SSRX_N_23") (pintype "bidirectional"))
    )
    (net (code "55") (name "P3_SSRX_P") (class "Default")
      (node (ref "JP3") (pin "6") (pinfunction "STDA_SSRX+_6") (pintype "bidirectional"))
      (node (ref "U1") (pin "22") (pinfunction "P3_SSRX_P_22") (pintype "bidirectional"))
    )
    (net (code "56") (name "P3_SSTX_N") (class "Default")
      (node (ref "C10") (pin "P$1") (pinfunction "1_P$1") (pintype "bidirectional"))
      (node (ref "U1") (pin "20") (pinfunction "P3_SSTX_N_20") (pintype "bidirectional"))
    )
    (net (code "57") (name "P3_SSTX_P") (class "Default")
      (node (ref "C9") (pin "P$1") (pinfunction "1_P$1") (pintype "bidirectional"))
      (node (ref "U1") (pin "19") (pinfunction "P3_SSTX_P_19") (pintype "bidirectional"))
    )
    (net (code "58") (name "P4_D_N") (class "Default")
      (node (ref "JP4") (pin "2") (pinfunction "D-_2") (pintype "bidirectional"))
      (node (ref "U1") (pin "25") (pinfunction "P4_D_N_25") (pintype "bidirectional"))
    )
    (net (code "59") (name "P4_D_P") (class "Default")
      (node (ref "JP4") (pin "3") (pinfunction "D+_3") (pintype "bidirectional"))
      (node (ref "U1") (pin "24") (pinfunction "P4_D_P_24") (pintype "bidirectional"))
    )
    (net (code "60") (name "P4_SSRX_N") (class "Default")
      (node (ref "JP4") (pin "5") (pinfunction "STDA_SSRX-_5") (pintype "bidirectional"))
      (node (ref "U1") (pin "30") (pinfunction "P4_SSRX_N_30") (pintype "bidirectional"))
    )
    (net (code "61") (name "P4_SSRX_P") (class "Default")
      (node (ref "JP4") (pin "6") (pinfunction "STDA_SSRX+_6") (pintype "bidirectional"))
      (node (ref "U1") (pin "29") (pinfunction "P4_SSRX_P_29") (pintype "bidirectional"))
    )
    (net (code "62") (name "P4_SSTX_N") (class "Default")
      (node (ref "C13") (pin "P$1") (pinfunction "1_P$1") (pintype "bidirectional"))
      (node (ref "U1") (pin "27") (pinfunction "P4_SSTX_N_27") (pintype "bidirectional"))
    )
    (net (code "63") (name "P4_SSTX_P") (class "Default")
      (node (ref "C14") (pin "P$1") (pinfunction "1_P$1") (pintype "bidirectional"))
      (node (ref "U1") (pin "26") (pinfunction "P4_SSTX_P_26") (pintype "bidirectional"))
    )
    (net (code "64") (name "PWRCTL1") (class "Default")
      (node (ref "R15") (pin "P$1") (pinfunction "1_P$1") (pintype "bidirectional"))
      (node (ref "U1") (pin "36") (pinfunction "PWRCTL1/BATEN1_36") (pintype "bidirectional"))
      (node (ref "U2") (pin "4") (pinfunction "EN_4") (pintype "bidirectional"))
    )
    (net (code "65") (name "PWRCTL2") (class "Default")
      (node (ref "R17") (pin "P$1") (pinfunction "1_P$1") (pintype "bidirectional"))
      (node (ref "U1") (pin "35") (pinfunction "PWRCTL2/BATEN2_35") (pintype "bidirectional"))
      (node (ref "U3") (pin "4") (pinfunction "EN_4") (pintype "bidirectional"))
    )
    (net (code "66") (name "PWRCTL3") (class "Default")
      (node (ref "U4") (pin "4") (pinfunction "EN_4") (pintype "bidirectional"))
    )
    (net (code "67") (name "PWRCTL4") (class "Default")
      (node (ref "U5") (pin "4") (pinfunction "EN_4") (pintype "bidirectional"))
    )
    (net (code "68") (name "US_CAP_SSTX_N") (class "Default")
      (node (ref "C29") (pin "P$1") (pinfunction "1_P$1") (pintype "bidirectional"))
      (node (ref "JP5") (pin "5") (pinfunction "STDB_SSTX-_5") (pintype "bidirectional"))
    )
    (net (code "69") (name "US_CAP_SSTX_P") (class "Default")
      (node (ref "C30") (pin "P$1") (pinfunction "1_P$1") (pintype "bidirectional"))
      (node (ref "JP5") (pin "6") (pinfunction "STDB_SSTX+_6") (pintype "bidirectional"))
    )
    (net (code "70") (name "US_D_N") (class "Default")
      (node (ref "JP5") (pin "2") (pinfunction "D-_2") (pintype "bidirectional"))
      (node (ref "U1") (pin "54") (pinfunction "US_D_N_54") (pintype "bidirectional"))
    )
    (net (code "71") (name "US_D_P") (class "Default")
      (node (ref "JP5") (pin "3") (pinfunction "D+_3") (pintype "bidirectional"))
      (node (ref "U1") (pin "53") (pinfunction "US_D_P_53") (pintype "bidirectional"))
    )
    (net (code "72") (name "US_SSRX_N") (class "Default")
      (node (ref "JP5") (pin "9") (pinfunction "STDB_SSRX+_9") (pintype "bidirectional"))
      (node (ref "U1") (pin "59") (pinfunction "US_SSRX_N_59") (pintype "bidirectional"))
    )
    (net (code "73") (name "US_SSRX_P") (class "Default")
      (node (ref "JP5") (pin "8") (pinfunction "STDB_SSRX-_8") (pintype "bidirectional"))
      (node (ref "U1") (pin "58") (pinfunction "US_SSRX_P_58") (pintype "bidirectional"))
    )
    (net (code "74") (name "US_SSTX_N") (class "Default")
      (node (ref "C30") (pin "P$2") (pinfunction "2_P$2") (pintype "bidirectional"))
      (node (ref "U1") (pin "56") (pinfunction "US_SSTX_N_56") (pintype "bidirectional"))
    )
    (net (code "75") (name "US_SSTX_P") (class "Default")
      (node (ref "C29") (pin "P$2") (pinfunction "2_P$2") (pintype "bidirectional"))
      (node (ref "U1") (pin "55") (pinfunction "US_SSTX_P_55") (pintype "bidirectional"))
    )
    (net (code "76") (name "US_VBUS") (class "Default")
      (node (ref "C33") (pin "1") (pinfunction "1_1") (pintype "bidirectional"))
      (node (ref "JP5") (pin "1") (pinfunction "VBUS_1") (pintype "bidirectional"))
      (node (ref "U1") (pin "48") (pinfunction "US_VBUS_48") (pintype "bidirectional"))
    )
    (net (code "77") (name "VDD11") (class "Default")
      (node (ref "C17") (pin "P$1") (pinfunction "1_P$1") (pintype "bidirectional"))
      (node (ref "C18") (pin "P$1") (pinfunction "1_P$1") (pintype "bidirectional"))
      (node (ref "C19") (pin "P$1") (pinfunction "1_P$1") (pintype "bidirectional"))
      (node (ref "C20") (pin "P$1") (pinfunction "1_P$1") (pintype "bidirectional"))
      (node (ref "C21") (pin "P$1") (pinfunction "1_P$1") (pintype "bidirectional"))
      (node (ref "C22") (pin "P$1") (pinfunction "1_P$1") (pintype "bidirectional"))
      (node (ref "C23") (pin "P$1") (pinfunction "1_P$1") (pintype "bidirectional"))
      (node (ref "C24") (pin "P$1") (pinfunction "1_P$1") (pintype "bidirectional"))
      (node (ref "C56") (pin "P$1") (pinfunction "1_P$1") (pintype "bidirectional"))
      (node (ref "C57") (pin "P$1") (pinfunction "1_P$1") (pintype "bidirectional"))
      (node (ref "C58") (pin "P$1") (pinfunction "1_P$1") (pintype "bidirectional"))
      (node (ref "C59") (pin "P$1") (pinfunction "1_P$1") (pintype "bidirectional"))
      (node (ref "C60") (pin "P$1") (pinfunction "1_P$1") (pintype "bidirectional"))
      (node (ref "C61") (pin "P$1") (pinfunction "1_P$1") (pintype "bidirectional"))
      (node (ref "C62") (pin "P$1") (pinfunction "1_P$1") (pintype "bidirectional"))
      (node (ref "C63") (pin "P$1") (pinfunction "1_P$1") (pintype "bidirectional"))
      (node (ref "C68") (pin "1") (pinfunction "1_1") (pintype "bidirectional"))
      (node (ref "FB1") (pin "P$1") (pinfunction "1_P$1") (pintype "bidirectional"))
      (node (ref "U1") (pin "13") (pinfunction "VDD11_13") (pintype "bidirectional"))
      (node (ref "U1") (pin "21") (pinfunction "VDD11_21") (pintype "bidirectional"))
      (node (ref "U1") (pin "28") (pinfunction "VDD11_28") (pintype "bidirectional"))
      (node (ref "U1") (pin "31") (pinfunction "VDD11_31") (pintype "bidirectional"))
      (node (ref "U1") (pin "5") (pinfunction "VDD11_5") (pintype "bidirectional"))
      (node (ref "U1") (pin "51") (pinfunction "VDD11_51") (pintype "bidirectional"))
      (node (ref "U1") (pin "57") (pinfunction "VDD11_57") (pintype "bidirectional"))
      (node (ref "U1") (pin "8") (pinfunction "VDD11_8") (pintype "bidirectional"))
    )
    (net (code "78") (name "VDD33") (class "Default")
      (node (ref "C25") (pin "P$1") (pinfunction "1_P$1") (pintype "bidirectional"))
      (node (ref "C26") (pin "P$1") (pinfunction "1_P$1") (pintype "bidirectional"))
      (node (ref "C27") (pin "P$1") (pinfunction "1_P$1") (pintype "bidirectional"))
      (node (ref "C28") (pin "P$1") (pinfunction "1_P$1") (pintype "bidirectional"))
      (node (ref "C64") (pin "P$1") (pinfunction "1_P$1") (pintype "bidirectional"))
      (node (ref "C65") (pin "P$1") (pinfunction "1_P$1") (pintype "bidirectional"))
      (node (ref "C66") (pin "P$1") (pinfunction "1_P$1") (pintype "bidirectional"))
      (node (ref "C67") (pin "P$1") (pinfunction "1_P$1") (pintype "bidirectional"))
      (node (ref "C69") (pin "1") (pinfunction "1_1") (pintype "bidirectional"))
      (node (ref "FB6") (pin "P$1") (pinfunction "1_P$1") (pintype "bidirectional"))
      (node (ref "R15") (pin "P$2") (pinfunction "2_P$2") (pintype "bidirectional"))
      (node (ref "R17") (pin "P$2") (pinfunction "2_P$2") (pintype "bidirectional"))
      (node (ref "U1") (pin "16") (pinfunction "VDD33_16") (pintype "bidirectional"))
      (node (ref "U1") (pin "34") (pinfunction "VDD33_34") (pintype "bidirectional"))
      (node (ref "U1") (pin "52") (pinfunction "VDD33_52") (pintype "bidirectional"))
      (node (ref "U1") (pin "63") (pinfunction "VDD33_63") (pintype "bidirectional"))
    )
    (net (code "79") (name "unconnected-(U1A-NC-Pad60)") (class "Default")
      (node (ref "U1") (pin "60") (pinfunction "NC_60") (pintype "bidirectional"))
    )
    (net (code "80") (name "unconnected-(U1B-AUTOENZ{slash}HS_SUSPEND-Pad45)") (class "Default")
      (node (ref "U1") (pin "45") (pinfunction "AUTOENZ/HS_SUSPEND_45") (pintype "bidirectional"))
    )
    (net (code "81") (name "unconnected-(U1B-PWRCTL_POL-Pad41)") (class "Default")
      (node (ref "U1") (pin "41") (pinfunction "PWRCTL_POL_41") (pintype "bidirectional"))
    )
    (net (code "82") (name "unconnected-(U1B-SCL{slash}SMBCLK-Pad38)") (class "Default")
      (node (ref "U1") (pin "38") (pinfunction "SCL/SMBCLK_38") (pintype "bidirectional"))
    )
    (net (code "83") (name "unconnected-(U1B-SDA{slash}SMBDAT-Pad37)") (class "Default")
      (node (ref "U1") (pin "37") (pinfunction "SDA/SMBDAT_37") (pintype "bidirectional"))
    )
    (net (code "84") (name "unconnected-(U1B-SMBUSZ{slash}SS_SUSPEND-Pad39)") (class "Default")
      (node (ref "U1") (pin "39") (pinfunction "SMBUSZ/SS_SUSPEND_39") (pintype "bidirectional"))
    )
    (net (code "85") (name "unconnected-(U1B-TEST-Pad49)") (class "Default")
      (node (ref "U1") (pin "49") (pinfunction "TEST_49") (pintype "bidirectional"))
    )
    (net (code "86") (name "unconnected-(U1C-PWRCTL3{slash}BATEN3-Pad33)") (class "Default")
      (node (ref "U1") (pin "33") (pinfunction "PWRCTL3/BATEN3_33") (pintype "bidirectional"))
    )
    (net (code "87") (name "unconnected-(U1C-PWRCTL4{slash}BATEN4-Pad32)") (class "Default")
      (node (ref "U1") (pin "32") (pinfunction "PWRCTL4/BATEN4_32") (pintype "bidirectional"))
    )
    (net (code "88") (name "unconnected-(U8-NC-Pad17)") (class "Default")
      (node (ref "U8") (pin "17") (pinfunction "NC_17") (pintype "bidirectional"))
    )
    (net (code "89") (name "unconnected-(U8-PG-Pad9)") (class "Default")
      (node (ref "U8") (pin "9") (pinfunction "PG_9") (pintype "bidirectional"))
    )
    (net (code "90") (name "unconnected-(U8-SS-Pad15)") (class "Default")
      (node (ref "U8") (pin "15") (pinfunction "SS_15") (pintype "bidirectional"))
    )
  )
)
